# Sheet2.net
KiCad netlist of a schematic drawn in Altium Designer
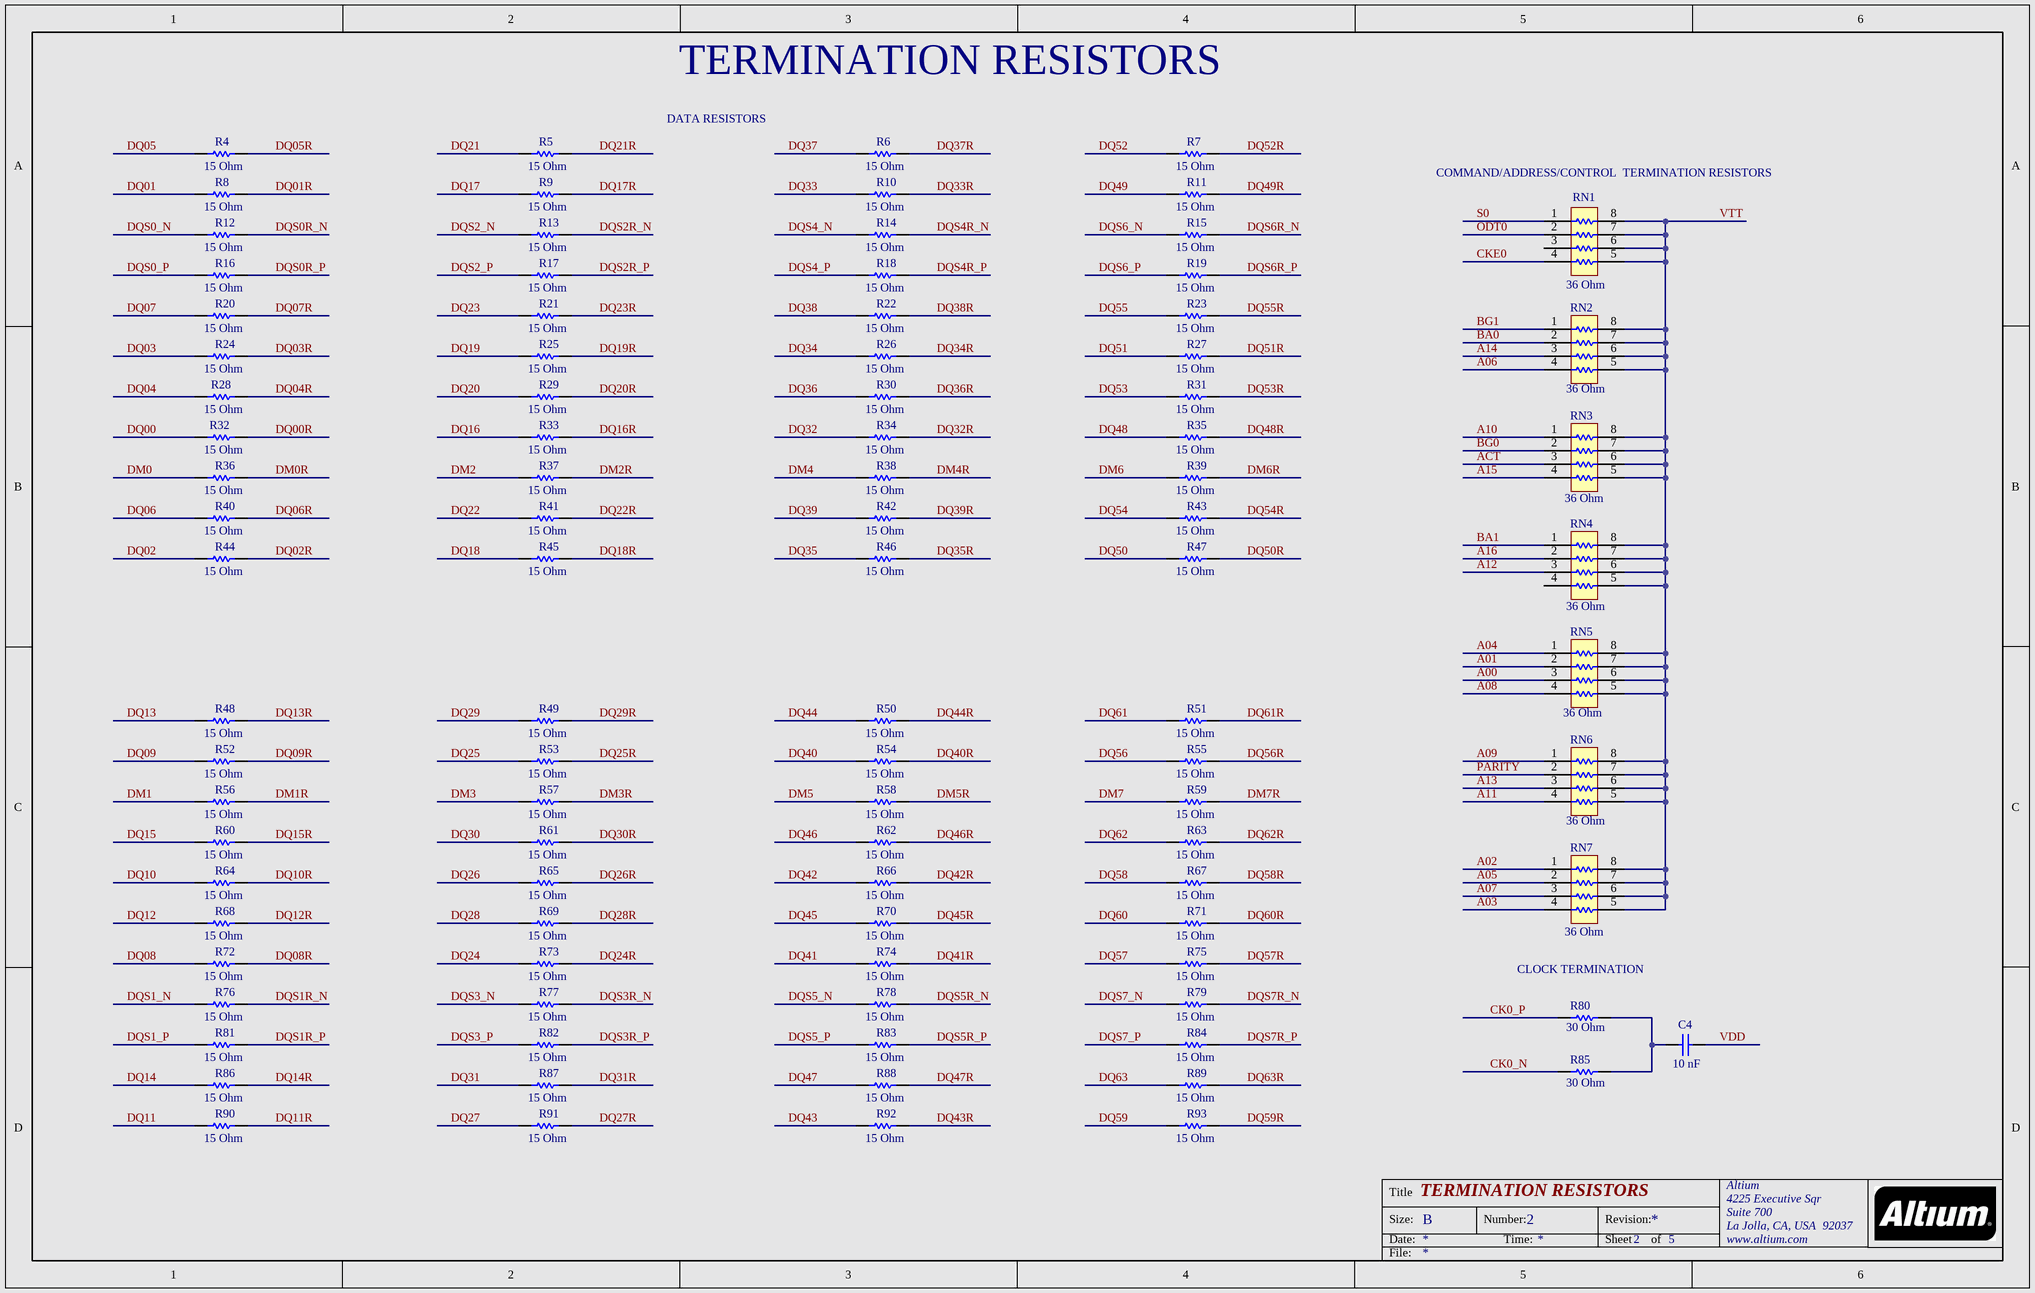
[diagram p0: Sheet2.SchDoc]

(export (version "E")
  (design (tool "Eeschema 10.0.6"))
  (components
    (comp (ref "C4")
      (value "C1005X7R1E103M050BB")
      (footprint "CAPC1005X55X10NL05")
      (description "Chip Capacitor, 10 nF, +/- 15%, 25 V, -55 to 125 degC, 0402 (1005 Metric), RoHS, Tape and Reel")
      (fields (field (name "TOLERANCE") "20%") (field (name "CAPACITANCE") "10 nF"))
      (libsource (lib "Altium Content Vault") (part "CMP-1663-00012-1"))
    )
    (comp (ref "R4")
      (value "ERJ-1GEJ150C")
      (footprint "RESC0603X26X15ML03T05")
      (description "Chip Resistor, 15 Ohm, +/- 5%, 0.05 W, -55 to 125 degC, 0201 (0603 Metric), RoHS, Tape and Reel")
      (fields (field (name "RESISTANCE") "15 Ohm") (field (name "TOLERANCE") "5%"))
      (libsource (lib "Altium Content Vault") (part "CMP-2004-03155-3"))
    )
    (comp (ref "R5")
      (value "ERJ-1GEJ150C")
      (footprint "RESC0603X26X15ML03T05")
      (description "Chip Resistor, 15 Ohm, +/- 5%, 0.05 W, -55 to 125 degC, 0201 (0603 Metric), RoHS, Tape and Reel")
      (fields (field (name "RESISTANCE") "15 Ohm") (field (name "TOLERANCE") "5%"))
      (libsource (lib "Altium Content Vault") (part "CMP-2004-03155-3"))
    )
    (comp (ref "R6")
      (value "ERJ-1GEJ150C")
      (footprint "RESC0603X26X15ML03T05")
      (description "Chip Resistor, 15 Ohm, +/- 5%, 0.05 W, -55 to 125 degC, 0201 (0603 Metric), RoHS, Tape and Reel")
      (fields (field (name "RESISTANCE") "15 Ohm") (field (name "TOLERANCE") "5%"))
      (libsource (lib "Altium Content Vault") (part "CMP-2004-03155-3"))
    )
    (comp (ref "R7")
      (value "ERJ-1GEJ150C")
      (footprint "RESC0603X26X15ML03T05")
      (description "Chip Resistor, 15 Ohm, +/- 5%, 0.05 W, -55 to 125 degC, 0201 (0603 Metric), RoHS, Tape and Reel")
      (fields (field (name "RESISTANCE") "15 Ohm") (field (name "TOLERANCE") "5%"))
      (libsource (lib "Altium Content Vault") (part "CMP-2004-03155-3"))
    )
    (comp (ref "R8")
      (value "ERJ-1GEJ150C")
      (footprint "RESC0603X26X15ML03T05")
      (description "Chip Resistor, 15 Ohm, +/- 5%, 0.05 W, -55 to 125 degC, 0201 (0603 Metric), RoHS, Tape and Reel")
      (fields (field (name "RESISTANCE") "15 Ohm") (field (name "TOLERANCE") "5%"))
      (libsource (lib "Altium Content Vault") (part "CMP-2004-03155-3"))
    )
    (comp (ref "R9")
      (value "ERJ-1GEJ150C")
      (footprint "RESC0603X26X15ML03T05")
      (description "Chip Resistor, 15 Ohm, +/- 5%, 0.05 W, -55 to 125 degC, 0201 (0603 Metric), RoHS, Tape and Reel")
      (fields (field (name "RESISTANCE") "15 Ohm") (field (name "TOLERANCE") "5%"))
      (libsource (lib "Altium Content Vault") (part "CMP-2004-03155-3"))
    )
    (comp (ref "R10")
      (value "ERJ-1GEJ150C")
      (footprint "RESC0603X26X15ML03T05")
      (description "Chip Resistor, 15 Ohm, +/- 5%, 0.05 W, -55 to 125 degC, 0201 (0603 Metric), RoHS, Tape and Reel")
      (fields (field (name "RESISTANCE") "15 Ohm") (field (name "TOLERANCE") "5%"))
      (libsource (lib "Altium Content Vault") (part "CMP-2004-03155-3"))
    )
    (comp (ref "R11")
      (value "ERJ-1GEJ150C")
      (footprint "RESC0603X26X15ML03T05")
      (description "Chip Resistor, 15 Ohm, +/- 5%, 0.05 W, -55 to 125 degC, 0201 (0603 Metric), RoHS, Tape and Reel")
      (fields (field (name "RESISTANCE") "15 Ohm") (field (name "TOLERANCE") "5%"))
      (libsource (lib "Altium Content Vault") (part "CMP-2004-03155-3"))
    )
    (comp (ref "R12")
      (value "ERJ-1GEJ150C")
      (footprint "RESC0603X26X15ML03T05")
      (description "Chip Resistor, 15 Ohm, +/- 5%, 0.05 W, -55 to 125 degC, 0201 (0603 Metric), RoHS, Tape and Reel")
      (fields (field (name "RESISTANCE") "15 Ohm") (field (name "TOLERANCE") "5%"))
      (libsource (lib "Altium Content Vault") (part "CMP-2004-03155-3"))
    )
    (comp (ref "R13")
      (value "ERJ-1GEJ150C")
      (footprint "RESC0603X26X15ML03T05")
      (description "Chip Resistor, 15 Ohm, +/- 5%, 0.05 W, -55 to 125 degC, 0201 (0603 Metric), RoHS, Tape and Reel")
      (fields (field (name "RESISTANCE") "15 Ohm") (field (name "TOLERANCE") "5%"))
      (libsource (lib "Altium Content Vault") (part "CMP-2004-03155-3"))
    )
    (comp (ref "R14")
      (value "ERJ-1GEJ150C")
      (footprint "RESC0603X26X15ML03T05")
      (description "Chip Resistor, 15 Ohm, +/- 5%, 0.05 W, -55 to 125 degC, 0201 (0603 Metric), RoHS, Tape and Reel")
      (fields (field (name "RESISTANCE") "15 Ohm") (field (name "TOLERANCE") "5%"))
      (libsource (lib "Altium Content Vault") (part "CMP-2004-03155-3"))
    )
    (comp (ref "R15")
      (value "ERJ-1GEJ150C")
      (footprint "RESC0603X26X15ML03T05")
      (description "Chip Resistor, 15 Ohm, +/- 5%, 0.05 W, -55 to 125 degC, 0201 (0603 Metric), RoHS, Tape and Reel")
      (fields (field (name "RESISTANCE") "15 Ohm") (field (name "TOLERANCE") "5%"))
      (libsource (lib "Altium Content Vault") (part "CMP-2004-03155-3"))
    )
    (comp (ref "R16")
      (value "ERJ-1GEJ150C")
      (footprint "RESC0603X26X15ML03T05")
      (description "Chip Resistor, 15 Ohm, +/- 5%, 0.05 W, -55 to 125 degC, 0201 (0603 Metric), RoHS, Tape and Reel")
      (fields (field (name "RESISTANCE") "15 Ohm") (field (name "TOLERANCE") "5%"))
      (libsource (lib "Altium Content Vault") (part "CMP-2004-03155-3"))
    )
    (comp (ref "R17")
      (value "ERJ-1GEJ150C")
      (footprint "RESC0603X26X15ML03T05")
      (description "Chip Resistor, 15 Ohm, +/- 5%, 0.05 W, -55 to 125 degC, 0201 (0603 Metric), RoHS, Tape and Reel")
      (fields (field (name "RESISTANCE") "15 Ohm") (field (name "TOLERANCE") "5%"))
      (libsource (lib "Altium Content Vault") (part "CMP-2004-03155-3"))
    )
    (comp (ref "R18")
      (value "ERJ-1GEJ150C")
      (footprint "RESC0603X26X15ML03T05")
      (description "Chip Resistor, 15 Ohm, +/- 5%, 0.05 W, -55 to 125 degC, 0201 (0603 Metric), RoHS, Tape and Reel")
      (fields (field (name "RESISTANCE") "15 Ohm") (field (name "TOLERANCE") "5%"))
      (libsource (lib "Altium Content Vault") (part "CMP-2004-03155-3"))
    )
    (comp (ref "R19")
      (value "ERJ-1GEJ150C")
      (footprint "RESC0603X26X15ML03T05")
      (description "Chip Resistor, 15 Ohm, +/- 5%, 0.05 W, -55 to 125 degC, 0201 (0603 Metric), RoHS, Tape and Reel")
      (fields (field (name "RESISTANCE") "15 Ohm") (field (name "TOLERANCE") "5%"))
      (libsource (lib "Altium Content Vault") (part "CMP-2004-03155-3"))
    )
    (comp (ref "R20")
      (value "ERJ-1GEJ150C")
      (footprint "RESC0603X26X15ML03T05")
      (description "Chip Resistor, 15 Ohm, +/- 5%, 0.05 W, -55 to 125 degC, 0201 (0603 Metric), RoHS, Tape and Reel")
      (fields (field (name "RESISTANCE") "15 Ohm") (field (name "TOLERANCE") "5%"))
      (libsource (lib "Altium Content Vault") (part "CMP-2004-03155-3"))
    )
    (comp (ref "R21")
      (value "ERJ-1GEJ150C")
      (footprint "RESC0603X26X15ML03T05")
      (description "Chip Resistor, 15 Ohm, +/- 5%, 0.05 W, -55 to 125 degC, 0201 (0603 Metric), RoHS, Tape and Reel")
      (fields (field (name "RESISTANCE") "15 Ohm") (field (name "TOLERANCE") "5%"))
      (libsource (lib "Altium Content Vault") (part "CMP-2004-03155-3"))
    )
    (comp (ref "R22")
      (value "ERJ-1GEJ150C")
      (footprint "RESC0603X26X15ML03T05")
      (description "Chip Resistor, 15 Ohm, +/- 5%, 0.05 W, -55 to 125 degC, 0201 (0603 Metric), RoHS, Tape and Reel")
      (fields (field (name "RESISTANCE") "15 Ohm") (field (name "TOLERANCE") "5%"))
      (libsource (lib "Altium Content Vault") (part "CMP-2004-03155-3"))
    )
    (comp (ref "R23")
      (value "ERJ-1GEJ150C")
      (footprint "RESC0603X26X15ML03T05")
      (description "Chip Resistor, 15 Ohm, +/- 5%, 0.05 W, -55 to 125 degC, 0201 (0603 Metric), RoHS, Tape and Reel")
      (fields (field (name "RESISTANCE") "15 Ohm") (field (name "TOLERANCE") "5%"))
      (libsource (lib "Altium Content Vault") (part "CMP-2004-03155-3"))
    )
    (comp (ref "R24")
      (value "ERJ-1GEJ150C")
      (footprint "RESC0603X26X15ML03T05")
      (description "Chip Resistor, 15 Ohm, +/- 5%, 0.05 W, -55 to 125 degC, 0201 (0603 Metric), RoHS, Tape and Reel")
      (fields (field (name "RESISTANCE") "15 Ohm") (field (name "TOLERANCE") "5%"))
      (libsource (lib "Altium Content Vault") (part "CMP-2004-03155-3"))
    )
    (comp (ref "R25")
      (value "ERJ-1GEJ150C")
      (footprint "RESC0603X26X15ML03T05")
      (description "Chip Resistor, 15 Ohm, +/- 5%, 0.05 W, -55 to 125 degC, 0201 (0603 Metric), RoHS, Tape and Reel")
      (fields (field (name "RESISTANCE") "15 Ohm") (field (name "TOLERANCE") "5%"))
      (libsource (lib "Altium Content Vault") (part "CMP-2004-03155-3"))
    )
    (comp (ref "R26")
      (value "ERJ-1GEJ150C")
      (footprint "RESC0603X26X15ML03T05")
      (description "Chip Resistor, 15 Ohm, +/- 5%, 0.05 W, -55 to 125 degC, 0201 (0603 Metric), RoHS, Tape and Reel")
      (fields (field (name "RESISTANCE") "15 Ohm") (field (name "TOLERANCE") "5%"))
      (libsource (lib "Altium Content Vault") (part "CMP-2004-03155-3"))
    )
    (comp (ref "R27")
      (value "ERJ-1GEJ150C")
      (footprint "RESC0603X26X15ML03T05")
      (description "Chip Resistor, 15 Ohm, +/- 5%, 0.05 W, -55 to 125 degC, 0201 (0603 Metric), RoHS, Tape and Reel")
      (fields (field (name "RESISTANCE") "15 Ohm") (field (name "TOLERANCE") "5%"))
      (libsource (lib "Altium Content Vault") (part "CMP-2004-03155-3"))
    )
    (comp (ref "R28")
      (value "ERJ-1GEJ150C")
      (footprint "RESC0603X26X15ML03T05")
      (description "Chip Resistor, 15 Ohm, +/- 5%, 0.05 W, -55 to 125 degC, 0201 (0603 Metric), RoHS, Tape and Reel")
      (fields (field (name "RESISTANCE") "15 Ohm") (field (name "TOLERANCE") "5%"))
      (libsource (lib "Altium Content Vault") (part "CMP-2004-03155-3"))
    )
    (comp (ref "R29")
      (value "ERJ-1GEJ150C")
      (footprint "RESC0603X26X15ML03T05")
      (description "Chip Resistor, 15 Ohm, +/- 5%, 0.05 W, -55 to 125 degC, 0201 (0603 Metric), RoHS, Tape and Reel")
      (fields (field (name "RESISTANCE") "15 Ohm") (field (name "TOLERANCE") "5%"))
      (libsource (lib "Altium Content Vault") (part "CMP-2004-03155-3"))
    )
    (comp (ref "R30")
      (value "ERJ-1GEJ150C")
      (footprint "RESC0603X26X15ML03T05")
      (description "Chip Resistor, 15 Ohm, +/- 5%, 0.05 W, -55 to 125 degC, 0201 (0603 Metric), RoHS, Tape and Reel")
      (fields (field (name "RESISTANCE") "15 Ohm") (field (name "TOLERANCE") "5%"))
      (libsource (lib "Altium Content Vault") (part "CMP-2004-03155-3"))
    )
    (comp (ref "R31")
      (value "ERJ-1GEJ150C")
      (footprint "RESC0603X26X15ML03T05")
      (description "Chip Resistor, 15 Ohm, +/- 5%, 0.05 W, -55 to 125 degC, 0201 (0603 Metric), RoHS, Tape and Reel")
      (fields (field (name "RESISTANCE") "15 Ohm") (field (name "TOLERANCE") "5%"))
      (libsource (lib "Altium Content Vault") (part "CMP-2004-03155-3"))
    )
    (comp (ref "R32")
      (value "ERJ-1GEJ150C")
      (footprint "RESC0603X26X15ML03T05")
      (description "Chip Resistor, 15 Ohm, +/- 5%, 0.05 W, -55 to 125 degC, 0201 (0603 Metric), RoHS, Tape and Reel")
      (fields (field (name "RESISTANCE") "15 Ohm") (field (name "TOLERANCE") "5%"))
      (libsource (lib "Altium Content Vault") (part "CMP-2004-03155-3"))
    )
    (comp (ref "R33")
      (value "ERJ-1GEJ150C")
      (footprint "RESC0603X26X15ML03T05")
      (description "Chip Resistor, 15 Ohm, +/- 5%, 0.05 W, -55 to 125 degC, 0201 (0603 Metric), RoHS, Tape and Reel")
      (fields (field (name "RESISTANCE") "15 Ohm") (field (name "TOLERANCE") "5%"))
      (libsource (lib "Altium Content Vault") (part "CMP-2004-03155-3"))
    )
    (comp (ref "R34")
      (value "ERJ-1GEJ150C")
      (footprint "RESC0603X26X15ML03T05")
      (description "Chip Resistor, 15 Ohm, +/- 5%, 0.05 W, -55 to 125 degC, 0201 (0603 Metric), RoHS, Tape and Reel")
      (fields (field (name "RESISTANCE") "15 Ohm") (field (name "TOLERANCE") "5%"))
      (libsource (lib "Altium Content Vault") (part "CMP-2004-03155-3"))
    )
    (comp (ref "R35")
      (value "ERJ-1GEJ150C")
      (footprint "RESC0603X26X15ML03T05")
      (description "Chip Resistor, 15 Ohm, +/- 5%, 0.05 W, -55 to 125 degC, 0201 (0603 Metric), RoHS, Tape and Reel")
      (fields (field (name "RESISTANCE") "15 Ohm") (field (name "TOLERANCE") "5%"))
      (libsource (lib "Altium Content Vault") (part "CMP-2004-03155-3"))
    )
    (comp (ref "R36")
      (value "ERJ-1GEJ150C")
      (footprint "RESC0603X26X15ML03T05")
      (description "Chip Resistor, 15 Ohm, +/- 5%, 0.05 W, -55 to 125 degC, 0201 (0603 Metric), RoHS, Tape and Reel")
      (fields (field (name "RESISTANCE") "15 Ohm") (field (name "TOLERANCE") "5%"))
      (libsource (lib "Altium Content Vault") (part "CMP-2004-03155-3"))
    )
    (comp (ref "R37")
      (value "ERJ-1GEJ150C")
      (footprint "RESC0603X26X15ML03T05")
      (description "Chip Resistor, 15 Ohm, +/- 5%, 0.05 W, -55 to 125 degC, 0201 (0603 Metric), RoHS, Tape and Reel")
      (fields (field (name "RESISTANCE") "15 Ohm") (field (name "TOLERANCE") "5%"))
      (libsource (lib "Altium Content Vault") (part "CMP-2004-03155-3"))
    )
    (comp (ref "R38")
      (value "ERJ-1GEJ150C")
      (footprint "RESC0603X26X15ML03T05")
      (description "Chip Resistor, 15 Ohm, +/- 5%, 0.05 W, -55 to 125 degC, 0201 (0603 Metric), RoHS, Tape and Reel")
      (fields (field (name "RESISTANCE") "15 Ohm") (field (name "TOLERANCE") "5%"))
      (libsource (lib "Altium Content Vault") (part "CMP-2004-03155-3"))
    )
    (comp (ref "R39")
      (value "ERJ-1GEJ150C")
      (footprint "RESC0603X26X15ML03T05")
      (description "Chip Resistor, 15 Ohm, +/- 5%, 0.05 W, -55 to 125 degC, 0201 (0603 Metric), RoHS, Tape and Reel")
      (fields (field (name "RESISTANCE") "15 Ohm") (field (name "TOLERANCE") "5%"))
      (libsource (lib "Altium Content Vault") (part "CMP-2004-03155-3"))
    )
    (comp (ref "R40")
      (value "ERJ-1GEJ150C")
      (footprint "RESC0603X26X15ML03T05")
      (description "Chip Resistor, 15 Ohm, +/- 5%, 0.05 W, -55 to 125 degC, 0201 (0603 Metric), RoHS, Tape and Reel")
      (fields (field (name "RESISTANCE") "15 Ohm") (field (name "TOLERANCE") "5%"))
      (libsource (lib "Altium Content Vault") (part "CMP-2004-03155-3"))
    )
    (comp (ref "R41")
      (value "ERJ-1GEJ150C")
      (footprint "RESC0603X26X15ML03T05")
      (description "Chip Resistor, 15 Ohm, +/- 5%, 0.05 W, -55 to 125 degC, 0201 (0603 Metric), RoHS, Tape and Reel")
      (fields (field (name "RESISTANCE") "15 Ohm") (field (name "TOLERANCE") "5%"))
      (libsource (lib "Altium Content Vault") (part "CMP-2004-03155-3"))
    )
    (comp (ref "R42")
      (value "ERJ-1GEJ150C")
      (footprint "RESC0603X26X15ML03T05")
      (description "Chip Resistor, 15 Ohm, +/- 5%, 0.05 W, -55 to 125 degC, 0201 (0603 Metric), RoHS, Tape and Reel")
      (fields (field (name "RESISTANCE") "15 Ohm") (field (name "TOLERANCE") "5%"))
      (libsource (lib "Altium Content Vault") (part "CMP-2004-03155-3"))
    )
    (comp (ref "R43")
      (value "ERJ-1GEJ150C")
      (footprint "RESC0603X26X15ML03T05")
      (description "Chip Resistor, 15 Ohm, +/- 5%, 0.05 W, -55 to 125 degC, 0201 (0603 Metric), RoHS, Tape and Reel")
      (fields (field (name "RESISTANCE") "15 Ohm") (field (name "TOLERANCE") "5%"))
      (libsource (lib "Altium Content Vault") (part "CMP-2004-03155-3"))
    )
    (comp (ref "R44")
      (value "ERJ-1GEJ150C")
      (footprint "RESC0603X26X15ML03T05")
      (description "Chip Resistor, 15 Ohm, +/- 5%, 0.05 W, -55 to 125 degC, 0201 (0603 Metric), RoHS, Tape and Reel")
      (fields (field (name "RESISTANCE") "15 Ohm") (field (name "TOLERANCE") "5%"))
      (libsource (lib "Altium Content Vault") (part "CMP-2004-03155-3"))
    )
    (comp (ref "R45")
      (value "ERJ-1GEJ150C")
      (footprint "RESC0603X26X15ML03T05")
      (description "Chip Resistor, 15 Ohm, +/- 5%, 0.05 W, -55 to 125 degC, 0201 (0603 Metric), RoHS, Tape and Reel")
      (fields (field (name "RESISTANCE") "15 Ohm") (field (name "TOLERANCE") "5%"))
      (libsource (lib "Altium Content Vault") (part "CMP-2004-03155-3"))
    )
    (comp (ref "R46")
      (value "ERJ-1GEJ150C")
      (footprint "RESC0603X26X15ML03T05")
      (description "Chip Resistor, 15 Ohm, +/- 5%, 0.05 W, -55 to 125 degC, 0201 (0603 Metric), RoHS, Tape and Reel")
      (fields (field (name "RESISTANCE") "15 Ohm") (field (name "TOLERANCE") "5%"))
      (libsource (lib "Altium Content Vault") (part "CMP-2004-03155-3"))
    )
    (comp (ref "R47")
      (value "ERJ-1GEJ150C")
      (footprint "RESC0603X26X15ML03T05")
      (description "Chip Resistor, 15 Ohm, +/- 5%, 0.05 W, -55 to 125 degC, 0201 (0603 Metric), RoHS, Tape and Reel")
      (fields (field (name "RESISTANCE") "15 Ohm") (field (name "TOLERANCE") "5%"))
      (libsource (lib "Altium Content Vault") (part "CMP-2004-03155-3"))
    )
    (comp (ref "R48")
      (value "ERJ-1GEJ150C")
      (footprint "RESC0603X26X15ML03T05")
      (description "Chip Resistor, 15 Ohm, +/- 5%, 0.05 W, -55 to 125 degC, 0201 (0603 Metric), RoHS, Tape and Reel")
      (fields (field (name "RESISTANCE") "15 Ohm") (field (name "TOLERANCE") "5%"))
      (libsource (lib "Altium Content Vault") (part "CMP-2004-03155-3"))
    )
    (comp (ref "R49")
      (value "ERJ-1GEJ150C")
      (footprint "RESC0603X26X15ML03T05")
      (description "Chip Resistor, 15 Ohm, +/- 5%, 0.05 W, -55 to 125 degC, 0201 (0603 Metric), RoHS, Tape and Reel")
      (fields (field (name "RESISTANCE") "15 Ohm") (field (name "TOLERANCE") "5%"))
      (libsource (lib "Altium Content Vault") (part "CMP-2004-03155-3"))
    )
    (comp (ref "R50")
      (value "ERJ-1GEJ150C")
      (footprint "RESC0603X26X15ML03T05")
      (description "Chip Resistor, 15 Ohm, +/- 5%, 0.05 W, -55 to 125 degC, 0201 (0603 Metric), RoHS, Tape and Reel")
      (fields (field (name "RESISTANCE") "15 Ohm") (field (name "TOLERANCE") "5%"))
      (libsource (lib "Altium Content Vault") (part "CMP-2004-03155-3"))
    )
    (comp (ref "R51")
      (value "ERJ-1GEJ150C")
      (footprint "RESC0603X26X15ML03T05")
      (description "Chip Resistor, 15 Ohm, +/- 5%, 0.05 W, -55 to 125 degC, 0201 (0603 Metric), RoHS, Tape and Reel")
      (fields (field (name "RESISTANCE") "15 Ohm") (field (name "TOLERANCE") "5%"))
      (libsource (lib "Altium Content Vault") (part "CMP-2004-03155-3"))
    )
    (comp (ref "R52")
      (value "ERJ-1GEJ150C")
      (footprint "RESC0603X26X15ML03T05")
      (description "Chip Resistor, 15 Ohm, +/- 5%, 0.05 W, -55 to 125 degC, 0201 (0603 Metric), RoHS, Tape and Reel")
      (fields (field (name "RESISTANCE") "15 Ohm") (field (name "TOLERANCE") "5%"))
      (libsource (lib "Altium Content Vault") (part "CMP-2004-03155-3"))
    )
    (comp (ref "R53")
      (value "ERJ-1GEJ150C")
      (footprint "RESC0603X26X15ML03T05")
      (description "Chip Resistor, 15 Ohm, +/- 5%, 0.05 W, -55 to 125 degC, 0201 (0603 Metric), RoHS, Tape and Reel")
      (fields (field (name "RESISTANCE") "15 Ohm") (field (name "TOLERANCE") "5%"))
      (libsource (lib "Altium Content Vault") (part "CMP-2004-03155-3"))
    )
    (comp (ref "R54")
      (value "ERJ-1GEJ150C")
      (footprint "RESC0603X26X15ML03T05")
      (description "Chip Resistor, 15 Ohm, +/- 5%, 0.05 W, -55 to 125 degC, 0201 (0603 Metric), RoHS, Tape and Reel")
      (fields (field (name "RESISTANCE") "15 Ohm") (field (name "TOLERANCE") "5%"))
      (libsource (lib "Altium Content Vault") (part "CMP-2004-03155-3"))
    )
    (comp (ref "R55")
      (value "ERJ-1GEJ150C")
      (footprint "RESC0603X26X15ML03T05")
      (description "Chip Resistor, 15 Ohm, +/- 5%, 0.05 W, -55 to 125 degC, 0201 (0603 Metric), RoHS, Tape and Reel")
      (fields (field (name "RESISTANCE") "15 Ohm") (field (name "TOLERANCE") "5%"))
      (libsource (lib "Altium Content Vault") (part "CMP-2004-03155-3"))
    )
    (comp (ref "R56")
      (value "ERJ-1GEJ150C")
      (footprint "RESC0603X26X15ML03T05")
      (description "Chip Resistor, 15 Ohm, +/- 5%, 0.05 W, -55 to 125 degC, 0201 (0603 Metric), RoHS, Tape and Reel")
      (fields (field (name "RESISTANCE") "15 Ohm") (field (name "TOLERANCE") "5%"))
      (libsource (lib "Altium Content Vault") (part "CMP-2004-03155-3"))
    )
    (comp (ref "R57")
      (value "ERJ-1GEJ150C")
      (footprint "RESC0603X26X15ML03T05")
      (description "Chip Resistor, 15 Ohm, +/- 5%, 0.05 W, -55 to 125 degC, 0201 (0603 Metric), RoHS, Tape and Reel")
      (fields (field (name "RESISTANCE") "15 Ohm") (field (name "TOLERANCE") "5%"))
      (libsource (lib "Altium Content Vault") (part "CMP-2004-03155-3"))
    )
    (comp (ref "R58")
      (value "ERJ-1GEJ150C")
      (footprint "RESC0603X26X15ML03T05")
      (description "Chip Resistor, 15 Ohm, +/- 5%, 0.05 W, -55 to 125 degC, 0201 (0603 Metric), RoHS, Tape and Reel")
      (fields (field (name "RESISTANCE") "15 Ohm") (field (name "TOLERANCE") "5%"))
      (libsource (lib "Altium Content Vault") (part "CMP-2004-03155-3"))
    )
    (comp (ref "R59")
      (value "ERJ-1GEJ150C")
      (footprint "RESC0603X26X15ML03T05")
      (description "Chip Resistor, 15 Ohm, +/- 5%, 0.05 W, -55 to 125 degC, 0201 (0603 Metric), RoHS, Tape and Reel")
      (fields (field (name "RESISTANCE") "15 Ohm") (field (name "TOLERANCE") "5%"))
      (libsource (lib "Altium Content Vault") (part "CMP-2004-03155-3"))
    )
    (comp (ref "R60")
      (value "ERJ-1GEJ150C")
      (footprint "RESC0603X26X15ML03T05")
      (description "Chip Resistor, 15 Ohm, +/- 5%, 0.05 W, -55 to 125 degC, 0201 (0603 Metric), RoHS, Tape and Reel")
      (fields (field (name "RESISTANCE") "15 Ohm") (field (name "TOLERANCE") "5%"))
      (libsource (lib "Altium Content Vault") (part "CMP-2004-03155-3"))
    )
    (comp (ref "R61")
      (value "ERJ-1GEJ150C")
      (footprint "RESC0603X26X15ML03T05")
      (description "Chip Resistor, 15 Ohm, +/- 5%, 0.05 W, -55 to 125 degC, 0201 (0603 Metric), RoHS, Tape and Reel")
      (fields (field (name "RESISTANCE") "15 Ohm") (field (name "TOLERANCE") "5%"))
      (libsource (lib "Altium Content Vault") (part "CMP-2004-03155-3"))
    )
    (comp (ref "R62")
      (value "ERJ-1GEJ150C")
      (footprint "RESC0603X26X15ML03T05")
      (description "Chip Resistor, 15 Ohm, +/- 5%, 0.05 W, -55 to 125 degC, 0201 (0603 Metric), RoHS, Tape and Reel")
      (fields (field (name "RESISTANCE") "15 Ohm") (field (name "TOLERANCE") "5%"))
      (libsource (lib "Altium Content Vault") (part "CMP-2004-03155-3"))
    )
    (comp (ref "R63")
      (value "ERJ-1GEJ150C")
      (footprint "RESC0603X26X15ML03T05")
      (description "Chip Resistor, 15 Ohm, +/- 5%, 0.05 W, -55 to 125 degC, 0201 (0603 Metric), RoHS, Tape and Reel")
      (fields (field (name "RESISTANCE") "15 Ohm") (field (name "TOLERANCE") "5%"))
      (libsource (lib "Altium Content Vault") (part "CMP-2004-03155-3"))
    )
    (comp (ref "R64")
      (value "ERJ-1GEJ150C")
      (footprint "RESC0603X26X15ML03T05")
      (description "Chip Resistor, 15 Ohm, +/- 5%, 0.05 W, -55 to 125 degC, 0201 (0603 Metric), RoHS, Tape and Reel")
      (fields (field (name "RESISTANCE") "15 Ohm") (field (name "TOLERANCE") "5%"))
      (libsource (lib "Altium Content Vault") (part "CMP-2004-03155-3"))
    )
    (comp (ref "R65")
      (value "ERJ-1GEJ150C")
      (footprint "RESC0603X26X15ML03T05")
      (description "Chip Resistor, 15 Ohm, +/- 5%, 0.05 W, -55 to 125 degC, 0201 (0603 Metric), RoHS, Tape and Reel")
      (fields (field (name "RESISTANCE") "15 Ohm") (field (name "TOLERANCE") "5%"))
      (libsource (lib "Altium Content Vault") (part "CMP-2004-03155-3"))
    )
    (comp (ref "R66")
      (value "ERJ-1GEJ150C")
      (footprint "RESC0603X26X15ML03T05")
      (description "Chip Resistor, 15 Ohm, +/- 5%, 0.05 W, -55 to 125 degC, 0201 (0603 Metric), RoHS, Tape and Reel")
      (fields (field (name "RESISTANCE") "15 Ohm") (field (name "TOLERANCE") "5%"))
      (libsource (lib "Altium Content Vault") (part "CMP-2004-03155-3"))
    )
    (comp (ref "R67")
      (value "ERJ-1GEJ150C")
      (footprint "RESC0603X26X15ML03T05")
      (description "Chip Resistor, 15 Ohm, +/- 5%, 0.05 W, -55 to 125 degC, 0201 (0603 Metric), RoHS, Tape and Reel")
      (fields (field (name "RESISTANCE") "15 Ohm") (field (name "TOLERANCE") "5%"))
      (libsource (lib "Altium Content Vault") (part "CMP-2004-03155-3"))
    )
    (comp (ref "R68")
      (value "ERJ-1GEJ150C")
      (footprint "RESC0603X26X15ML03T05")
      (description "Chip Resistor, 15 Ohm, +/- 5%, 0.05 W, -55 to 125 degC, 0201 (0603 Metric), RoHS, Tape and Reel")
      (fields (field (name "RESISTANCE") "15 Ohm") (field (name "TOLERANCE") "5%"))
      (libsource (lib "Altium Content Vault") (part "CMP-2004-03155-3"))
    )
    (comp (ref "R69")
      (value "ERJ-1GEJ150C")
      (footprint "RESC0603X26X15ML03T05")
      (description "Chip Resistor, 15 Ohm, +/- 5%, 0.05 W, -55 to 125 degC, 0201 (0603 Metric), RoHS, Tape and Reel")
      (fields (field (name "RESISTANCE") "15 Ohm") (field (name "TOLERANCE") "5%"))
      (libsource (lib "Altium Content Vault") (part "CMP-2004-03155-3"))
    )
    (comp (ref "R70")
      (value "ERJ-1GEJ150C")
      (footprint "RESC0603X26X15ML03T05")
      (description "Chip Resistor, 15 Ohm, +/- 5%, 0.05 W, -55 to 125 degC, 0201 (0603 Metric), RoHS, Tape and Reel")
      (fields (field (name "RESISTANCE") "15 Ohm") (field (name "TOLERANCE") "5%"))
      (libsource (lib "Altium Content Vault") (part "CMP-2004-03155-3"))
    )
    (comp (ref "R71")
      (value "ERJ-1GEJ150C")
      (footprint "RESC0603X26X15ML03T05")
      (description "Chip Resistor, 15 Ohm, +/- 5%, 0.05 W, -55 to 125 degC, 0201 (0603 Metric), RoHS, Tape and Reel")
      (fields (field (name "RESISTANCE") "15 Ohm") (field (name "TOLERANCE") "5%"))
      (libsource (lib "Altium Content Vault") (part "CMP-2004-03155-3"))
    )
    (comp (ref "R72")
      (value "ERJ-1GEJ150C")
      (footprint "RESC0603X26X15ML03T05")
      (description "Chip Resistor, 15 Ohm, +/- 5%, 0.05 W, -55 to 125 degC, 0201 (0603 Metric), RoHS, Tape and Reel")
      (fields (field (name "RESISTANCE") "15 Ohm") (field (name "TOLERANCE") "5%"))
      (libsource (lib "Altium Content Vault") (part "CMP-2004-03155-3"))
    )
    (comp (ref "R73")
      (value "ERJ-1GEJ150C")
      (footprint "RESC0603X26X15ML03T05")
      (description "Chip Resistor, 15 Ohm, +/- 5%, 0.05 W, -55 to 125 degC, 0201 (0603 Metric), RoHS, Tape and Reel")
      (fields (field (name "RESISTANCE") "15 Ohm") (field (name "TOLERANCE") "5%"))
      (libsource (lib "Altium Content Vault") (part "CMP-2004-03155-3"))
    )
    (comp (ref "R74")
      (value "ERJ-1GEJ150C")
      (footprint "RESC0603X26X15ML03T05")
      (description "Chip Resistor, 15 Ohm, +/- 5%, 0.05 W, -55 to 125 degC, 0201 (0603 Metric), RoHS, Tape and Reel")
      (fields (field (name "RESISTANCE") "15 Ohm") (field (name "TOLERANCE") "5%"))
      (libsource (lib "Altium Content Vault") (part "CMP-2004-03155-3"))
    )
    (comp (ref "R75")
      (value "ERJ-1GEJ150C")
      (footprint "RESC0603X26X15ML03T05")
      (description "Chip Resistor, 15 Ohm, +/- 5%, 0.05 W, -55 to 125 degC, 0201 (0603 Metric), RoHS, Tape and Reel")
      (fields (field (name "RESISTANCE") "15 Ohm") (field (name "TOLERANCE") "5%"))
      (libsource (lib "Altium Content Vault") (part "CMP-2004-03155-3"))
    )
    (comp (ref "R76")
      (value "ERJ-1GEJ150C")
      (footprint "RESC0603X26X15ML03T05")
      (description "Chip Resistor, 15 Ohm, +/- 5%, 0.05 W, -55 to 125 degC, 0201 (0603 Metric), RoHS, Tape and Reel")
      (fields (field (name "RESISTANCE") "15 Ohm") (field (name "TOLERANCE") "5%"))
      (libsource (lib "Altium Content Vault") (part "CMP-2004-03155-3"))
    )
    (comp (ref "R77")
      (value "ERJ-1GEJ150C")
      (footprint "RESC0603X26X15ML03T05")
      (description "Chip Resistor, 15 Ohm, +/- 5%, 0.05 W, -55 to 125 degC, 0201 (0603 Metric), RoHS, Tape and Reel")
      (fields (field (name "RESISTANCE") "15 Ohm") (field (name "TOLERANCE") "5%"))
      (libsource (lib "Altium Content Vault") (part "CMP-2004-03155-3"))
    )
    (comp (ref "R78")
      (value "ERJ-1GEJ150C")
      (footprint "RESC0603X26X15ML03T05")
      (description "Chip Resistor, 15 Ohm, +/- 5%, 0.05 W, -55 to 125 degC, 0201 (0603 Metric), RoHS, Tape and Reel")
      (fields (field (name "RESISTANCE") "15 Ohm") (field (name "TOLERANCE") "5%"))
      (libsource (lib "Altium Content Vault") (part "CMP-2004-03155-3"))
    )
    (comp (ref "R79")
      (value "ERJ-1GEJ150C")
      (footprint "RESC0603X26X15ML03T05")
      (description "Chip Resistor, 15 Ohm, +/- 5%, 0.05 W, -55 to 125 degC, 0201 (0603 Metric), RoHS, Tape and Reel")
      (fields (field (name "RESISTANCE") "15 Ohm") (field (name "TOLERANCE") "5%"))
      (libsource (lib "Altium Content Vault") (part "CMP-2004-03155-3"))
    )
    (comp (ref "R80")
      (value "RC0402JR-0730RL")
      (footprint "RESC1005X40X25NL5T10")
      (description "Chip Resistor, 30 Ohm, +/- 5%, 0.063 W, -55 to 155 degC, 0402 (1005 Metric), RoHS, Tape and Reel")
      (fields (field (name "RESISTANCE") "30 Ohm") (field (name "TOLERANCE") "5%"))
      (libsource (lib "Altium Content Vault") (part "CMP-2002-07983-2"))
    )
    (comp (ref "R81")
      (value "ERJ-1GEJ150C")
      (footprint "RESC0603X26X15ML03T05")
      (description "Chip Resistor, 15 Ohm, +/- 5%, 0.05 W, -55 to 125 degC, 0201 (0603 Metric), RoHS, Tape and Reel")
      (fields (field (name "RESISTANCE") "15 Ohm") (field (name "TOLERANCE") "5%"))
      (libsource (lib "Altium Content Vault") (part "CMP-2004-03155-3"))
    )
    (comp (ref "R82")
      (value "ERJ-1GEJ150C")
      (footprint "RESC0603X26X15ML03T05")
      (description "Chip Resistor, 15 Ohm, +/- 5%, 0.05 W, -55 to 125 degC, 0201 (0603 Metric), RoHS, Tape and Reel")
      (fields (field (name "RESISTANCE") "15 Ohm") (field (name "TOLERANCE") "5%"))
      (libsource (lib "Altium Content Vault") (part "CMP-2004-03155-3"))
    )
    (comp (ref "R83")
      (value "ERJ-1GEJ150C")
      (footprint "RESC0603X26X15ML03T05")
      (description "Chip Resistor, 15 Ohm, +/- 5%, 0.05 W, -55 to 125 degC, 0201 (0603 Metric), RoHS, Tape and Reel")
      (fields (field (name "RESISTANCE") "15 Ohm") (field (name "TOLERANCE") "5%"))
      (libsource (lib "Altium Content Vault") (part "CMP-2004-03155-3"))
    )
    (comp (ref "R84")
      (value "ERJ-1GEJ150C")
      (footprint "RESC0603X26X15ML03T05")
      (description "Chip Resistor, 15 Ohm, +/- 5%, 0.05 W, -55 to 125 degC, 0201 (0603 Metric), RoHS, Tape and Reel")
      (fields (field (name "RESISTANCE") "15 Ohm") (field (name "TOLERANCE") "5%"))
      (libsource (lib "Altium Content Vault") (part "CMP-2004-03155-3"))
    )
    (comp (ref "R85")
      (value "RC0402JR-0730RL")
      (footprint "RESC1005X40X25NL5T10")
      (description "Chip Resistor, 30 Ohm, +/- 5%, 0.063 W, -55 to 155 degC, 0402 (1005 Metric), RoHS, Tape and Reel")
      (fields (field (name "RESISTANCE") "30 Ohm") (field (name "TOLERANCE") "5%"))
      (libsource (lib "Altium Content Vault") (part "CMP-2002-07983-2"))
    )
    (comp (ref "R86")
      (value "ERJ-1GEJ150C")
      (footprint "RESC0603X26X15ML03T05")
      (description "Chip Resistor, 15 Ohm, +/- 5%, 0.05 W, -55 to 125 degC, 0201 (0603 Metric), RoHS, Tape and Reel")
      (fields (field (name "RESISTANCE") "15 Ohm") (field (name "TOLERANCE") "5%"))
      (libsource (lib "Altium Content Vault") (part "CMP-2004-03155-3"))
    )
    (comp (ref "R87")
      (value "ERJ-1GEJ150C")
      (footprint "RESC0603X26X15ML03T05")
      (description "Chip Resistor, 15 Ohm, +/- 5%, 0.05 W, -55 to 125 degC, 0201 (0603 Metric), RoHS, Tape and Reel")
      (fields (field (name "RESISTANCE") "15 Ohm") (field (name "TOLERANCE") "5%"))
      (libsource (lib "Altium Content Vault") (part "CMP-2004-03155-3"))
    )
    (comp (ref "R88")
      (value "ERJ-1GEJ150C")
      (footprint "RESC0603X26X15ML03T05")
      (description "Chip Resistor, 15 Ohm, +/- 5%, 0.05 W, -55 to 125 degC, 0201 (0603 Metric), RoHS, Tape and Reel")
      (fields (field (name "RESISTANCE") "15 Ohm") (field (name "TOLERANCE") "5%"))
      (libsource (lib "Altium Content Vault") (part "CMP-2004-03155-3"))
    )
    (comp (ref "R89")
      (value "ERJ-1GEJ150C")
      (footprint "RESC0603X26X15ML03T05")
      (description "Chip Resistor, 15 Ohm, +/- 5%, 0.05 W, -55 to 125 degC, 0201 (0603 Metric), RoHS, Tape and Reel")
      (fields (field (name "RESISTANCE") "15 Ohm") (field (name "TOLERANCE") "5%"))
      (libsource (lib "Altium Content Vault") (part "CMP-2004-03155-3"))
    )
    (comp (ref "R90")
      (value "ERJ-1GEJ150C")
      (footprint "RESC0603X26X15ML03T05")
      (description "Chip Resistor, 15 Ohm, +/- 5%, 0.05 W, -55 to 125 degC, 0201 (0603 Metric), RoHS, Tape and Reel")
      (fields (field (name "RESISTANCE") "15 Ohm") (field (name "TOLERANCE") "5%"))
      (libsource (lib "Altium Content Vault") (part "CMP-2004-03155-3"))
    )
    (comp (ref "R91")
      (value "ERJ-1GEJ150C")
      (footprint "RESC0603X26X15ML03T05")
      (description "Chip Resistor, 15 Ohm, +/- 5%, 0.05 W, -55 to 125 degC, 0201 (0603 Metric), RoHS, Tape and Reel")
      (fields (field (name "RESISTANCE") "15 Ohm") (field (name "TOLERANCE") "5%"))
      (libsource (lib "Altium Content Vault") (part "CMP-2004-03155-3"))
    )
    (comp (ref "R92")
      (value "ERJ-1GEJ150C")
      (footprint "RESC0603X26X15ML03T05")
      (description "Chip Resistor, 15 Ohm, +/- 5%, 0.05 W, -55 to 125 degC, 0201 (0603 Metric), RoHS, Tape and Reel")
      (fields (field (name "RESISTANCE") "15 Ohm") (field (name "TOLERANCE") "5%"))
      (libsource (lib "Altium Content Vault") (part "CMP-2004-03155-3"))
    )
    (comp (ref "R93")
      (value "ERJ-1GEJ150C")
      (footprint "RESC0603X26X15ML03T05")
      (description "Chip Resistor, 15 Ohm, +/- 5%, 0.05 W, -55 to 125 degC, 0201 (0603 Metric), RoHS, Tape and Reel")
      (fields (field (name "RESISTANCE") "15 Ohm") (field (name "TOLERANCE") "5%"))
      (libsource (lib "Altium Content Vault") (part "CMP-2004-03155-3"))
    )
    (comp (ref "RN1")
      (value "CAY10-360J4LF")
      (footprint "BOUR-CAY10-J4_V")
      (description "Chip Resistor Array, 36 Ohm, +/- 5%, 62.5 mW, -55 to 125 degC, 8-Pin SMD, RoHS, Tape and Reel")
      (fields (field (name "RESISTANCE") "36 Ohm") (field (name "TOLERANCE") "5%"))
      (libsource (lib "Altium Content Vault") (part "CMP-1734-00001-1"))
    )
    (comp (ref "RN2")
      (value "CAY10-360J4LF")
      (footprint "BOUR-CAY10-J4_V")
      (description "Chip Resistor Array, 36 Ohm, +/- 5%, 62.5 mW, -55 to 125 degC, 8-Pin SMD, RoHS, Tape and Reel")
      (fields (field (name "RESISTANCE") "36 Ohm") (field (name "TOLERANCE") "5%"))
      (libsource (lib "Altium Content Vault") (part "CMP-1734-00001-1"))
    )
    (comp (ref "RN3")
      (value "CAY10-360J4LF")
      (footprint "BOUR-CAY10-J4_V")
      (description "Chip Resistor Array, 36 Ohm, +/- 5%, 62.5 mW, -55 to 125 degC, 8-Pin SMD, RoHS, Tape and Reel")
      (fields (field (name "RESISTANCE") "36 Ohm") (field (name "TOLERANCE") "5%"))
      (libsource (lib "Altium Content Vault") (part "CMP-1734-00001-1"))
    )
    (comp (ref "RN4")
      (value "CAY10-360J4LF")
      (footprint "BOUR-CAY10-J4_V")
      (description "Chip Resistor Array, 36 Ohm, +/- 5%, 62.5 mW, -55 to 125 degC, 8-Pin SMD, RoHS, Tape and Reel")
      (fields (field (name "RESISTANCE") "36 Ohm") (field (name "TOLERANCE") "5%"))
      (libsource (lib "Altium Content Vault") (part "CMP-1734-00001-1"))
    )
    (comp (ref "RN5")
      (value "CAY10-360J4LF")
      (footprint "BOUR-CAY10-J4_V")
      (description "Chip Resistor Array, 36 Ohm, +/- 5%, 62.5 mW, -55 to 125 degC, 8-Pin SMD, RoHS, Tape and Reel")
      (fields (field (name "RESISTANCE") "36 Ohm") (field (name "TOLERANCE") "5%"))
      (libsource (lib "Altium Content Vault") (part "CMP-1734-00001-1"))
    )
    (comp (ref "RN6")
      (value "CAY10-360J4LF")
      (footprint "BOUR-CAY10-J4_V")
      (description "Chip Resistor Array, 36 Ohm, +/- 5%, 62.5 mW, -55 to 125 degC, 8-Pin SMD, RoHS, Tape and Reel")
      (fields (field (name "RESISTANCE") "36 Ohm") (field (name "TOLERANCE") "5%"))
      (libsource (lib "Altium Content Vault") (part "CMP-1734-00001-1"))
    )
    (comp (ref "RN7")
      (value "CAY10-360J4LF")
      (footprint "BOUR-CAY10-J4_V")
      (description "Chip Resistor Array, 36 Ohm, +/- 5%, 62.5 mW, -55 to 125 degC, 8-Pin SMD, RoHS, Tape and Reel")
      (fields (field (name "RESISTANCE") "36 Ohm") (field (name "TOLERANCE") "5%"))
      (libsource (lib "Altium Content Vault") (part "CMP-1734-00001-1"))
    )
  )
  (nets
    (net (code "1") (name "/A00") (class "Default")
      (node (ref "RN5") (pin "3") (pinfunction "3_3") (pintype "passive"))
    )
    (net (code "2") (name "/A01") (class "Default")
      (node (ref "RN5") (pin "2") (pinfunction "2_2") (pintype "passive"))
    )
    (net (code "3") (name "/A02") (class "Default")
      (node (ref "RN7") (pin "1") (pinfunction "1_1") (pintype "passive"))
    )
    (net (code "4") (name "/A03") (class "Default")
      (node (ref "RN7") (pin "4") (pinfunction "4_4") (pintype "passive"))
    )
    (net (code "5") (name "/A04") (class "Default")
      (node (ref "RN5") (pin "1") (pinfunction "1_1") (pintype "passive"))
    )
    (net (code "6") (name "/A05") (class "Default")
      (node (ref "RN7") (pin "2") (pinfunction "2_2") (pintype "passive"))
    )
    (net (code "7") (name "/A06") (class "Default")
      (node (ref "RN2") (pin "4") (pinfunction "4_4") (pintype "passive"))
    )
    (net (code "8") (name "/A07") (class "Default")
      (node (ref "RN7") (pin "3") (pinfunction "3_3") (pintype "passive"))
    )
    (net (code "9") (name "/A08") (class "Default")
      (node (ref "RN5") (pin "4") (pinfunction "4_4") (pintype "passive"))
    )
    (net (code "10") (name "/A09") (class "Default")
      (node (ref "RN6") (pin "1") (pinfunction "1_1") (pintype "passive"))
    )
    (net (code "11") (name "/A10") (class "Default")
      (node (ref "RN3") (pin "1") (pinfunction "1_1") (pintype "passive"))
    )
    (net (code "12") (name "/A11") (class "Default")
      (node (ref "RN6") (pin "4") (pinfunction "4_4") (pintype "passive"))
    )
    (net (code "13") (name "/A12") (class "Default")
      (node (ref "RN4") (pin "3") (pinfunction "3_3") (pintype "passive"))
    )
    (net (code "14") (name "/A13") (class "Default")
      (node (ref "RN6") (pin "3") (pinfunction "3_3") (pintype "passive"))
    )
    (net (code "15") (name "/A14") (class "Default")
      (node (ref "RN2") (pin "3") (pinfunction "3_3") (pintype "passive"))
    )
    (net (code "16") (name "/A15") (class "Default")
      (node (ref "RN3") (pin "4") (pinfunction "4_4") (pintype "passive"))
    )
    (net (code "17") (name "/A16") (class "Default")
      (node (ref "RN4") (pin "2") (pinfunction "2_2") (pintype "passive"))
    )
    (net (code "18") (name "/ACT") (class "Default")
      (node (ref "RN3") (pin "3") (pinfunction "3_3") (pintype "passive"))
    )
    (net (code "19") (name "/BA0") (class "Default")
      (node (ref "RN2") (pin "2") (pinfunction "2_2") (pintype "passive"))
    )
    (net (code "20") (name "/BA1") (class "Default")
      (node (ref "RN4") (pin "1") (pinfunction "1_1") (pintype "passive"))
    )
    (net (code "21") (name "/BG0") (class "Default")
      (node (ref "RN3") (pin "2") (pinfunction "2_2") (pintype "passive"))
    )
    (net (code "22") (name "/BG1") (class "Default")
      (node (ref "RN2") (pin "1") (pinfunction "1_1") (pintype "passive"))
    )
    (net (code "23") (name "/CK0_N") (class "Default")
      (node (ref "R85") (pin "1") (pinfunction "1_1") (pintype "passive"))
    )
    (net (code "24") (name "/CK0_P") (class "Default")
      (node (ref "R80") (pin "1") (pinfunction "1_1") (pintype "passive"))
    )
    (net (code "25") (name "/CKE0") (class "Default")
      (node (ref "RN1") (pin "4") (pinfunction "4_4") (pintype "passive"))
    )
    (net (code "26") (name "/DM0") (class "Default")
      (node (ref "R36") (pin "1") (pinfunction "1_1") (pintype "passive"))
    )
    (net (code "27") (name "/DM0R") (class "Default")
      (node (ref "R36") (pin "2") (pinfunction "2_2") (pintype "passive"))
    )
    (net (code "28") (name "/DM1") (class "Default")
      (node (ref "R56") (pin "1") (pinfunction "1_1") (pintype "passive"))
    )
    (net (code "29") (name "/DM1R") (class "Default")
      (node (ref "R56") (pin "2") (pinfunction "2_2") (pintype "passive"))
    )
    (net (code "30") (name "/DM2") (class "Default")
      (node (ref "R37") (pin "1") (pinfunction "1_1") (pintype "passive"))
    )
    (net (code "31") (name "/DM2R") (class "Default")
      (node (ref "R37") (pin "2") (pinfunction "2_2") (pintype "passive"))
    )
    (net (code "32") (name "/DM3") (class "Default")
      (node (ref "R57") (pin "1") (pinfunction "1_1") (pintype "passive"))
    )
    (net (code "33") (name "/DM3R") (class "Default")
      (node (ref "R57") (pin "2") (pinfunction "2_2") (pintype "passive"))
    )
    (net (code "34") (name "/DM4") (class "Default")
      (node (ref "R38") (pin "1") (pinfunction "1_1") (pintype "passive"))
    )
    (net (code "35") (name "/DM4R") (class "Default")
      (node (ref "R38") (pin "2") (pinfunction "2_2") (pintype "passive"))
    )
    (net (code "36") (name "/DM5") (class "Default")
      (node (ref "R58") (pin "1") (pinfunction "1_1") (pintype "passive"))
    )
    (net (code "37") (name "/DM5R") (class "Default")
      (node (ref "R58") (pin "2") (pinfunction "2_2") (pintype "passive"))
    )
    (net (code "38") (name "/DM6") (class "Default")
      (node (ref "R39") (pin "1") (pinfunction "1_1") (pintype "passive"))
    )
    (net (code "39") (name "/DM6R") (class "Default")
      (node (ref "R39") (pin "2") (pinfunction "2_2") (pintype "passive"))
    )
    (net (code "40") (name "/DM7") (class "Default")
      (node (ref "R59") (pin "1") (pinfunction "1_1") (pintype "passive"))
    )
    (net (code "41") (name "/DM7R") (class "Default")
      (node (ref "R59") (pin "2") (pinfunction "2_2") (pintype "passive"))
    )
    (net (code "42") (name "/DQ00") (class "Default")
      (node (ref "R32") (pin "1") (pinfunction "1_1") (pintype "passive"))
    )
    (net (code "43") (name "/DQ00R") (class "Default")
      (node (ref "R32") (pin "2") (pinfunction "2_2") (pintype "passive"))
    )
    (net (code "44") (name "/DQ01") (class "Default")
      (node (ref "R8") (pin "1") (pinfunction "1_1") (pintype "passive"))
    )
    (net (code "45") (name "/DQ01R") (class "Default")
      (node (ref "R8") (pin "2") (pinfunction "2_2") (pintype "passive"))
    )
    (net (code "46") (name "/DQ02") (class "Default")
      (node (ref "R44") (pin "1") (pinfunction "1_1") (pintype "passive"))
    )
    (net (code "47") (name "/DQ02R") (class "Default")
      (node (ref "R44") (pin "2") (pinfunction "2_2") (pintype "passive"))
    )
    (net (code "48") (name "/DQ03") (class "Default")
      (node (ref "R24") (pin "1") (pinfunction "1_1") (pintype "passive"))
    )
    (net (code "49") (name "/DQ03R") (class "Default")
      (node (ref "R24") (pin "2") (pinfunction "2_2") (pintype "passive"))
    )
    (net (code "50") (name "/DQ04") (class "Default")
      (node (ref "R28") (pin "1") (pinfunction "1_1") (pintype "passive"))
    )
    (net (code "51") (name "/DQ04R") (class "Default")
      (node (ref "R28") (pin "2") (pinfunction "2_2") (pintype "passive"))
    )
    (net (code "52") (name "/DQ05") (class "Default")
      (node (ref "R4") (pin "1") (pinfunction "1_1") (pintype "passive"))
    )
    (net (code "53") (name "/DQ05R") (class "Default")
      (node (ref "R4") (pin "2") (pinfunction "2_2") (pintype "passive"))
    )
    (net (code "54") (name "/DQ06") (class "Default")
      (node (ref "R40") (pin "1") (pinfunction "1_1") (pintype "passive"))
    )
    (net (code "55") (name "/DQ06R") (class "Default")
      (node (ref "R40") (pin "2") (pinfunction "2_2") (pintype "passive"))
    )
    (net (code "56") (name "/DQ07") (class "Default")
      (node (ref "R20") (pin "1") (pinfunction "1_1") (pintype "passive"))
    )
    (net (code "57") (name "/DQ07R") (class "Default")
      (node (ref "R20") (pin "2") (pinfunction "2_2") (pintype "passive"))
    )
    (net (code "58") (name "/DQ08") (class "Default")
      (node (ref "R72") (pin "1") (pinfunction "1_1") (pintype "passive"))
    )
    (net (code "59") (name "/DQ08R") (class "Default")
      (node (ref "R72") (pin "2") (pinfunction "2_2") (pintype "passive"))
    )
    (net (code "60") (name "/DQ09") (class "Default")
      (node (ref "R52") (pin "1") (pinfunction "1_1") (pintype "passive"))
    )
    (net (code "61") (name "/DQ09R") (class "Default")
      (node (ref "R52") (pin "2") (pinfunction "2_2") (pintype "passive"))
    )
    (net (code "62") (name "/DQ10") (class "Default")
      (node (ref "R64") (pin "1") (pinfunction "1_1") (pintype "passive"))
    )
    (net (code "63") (name "/DQ10R") (class "Default")
      (node (ref "R64") (pin "2") (pinfunction "2_2") (pintype "passive"))
    )
    (net (code "64") (name "/DQ11") (class "Default")
      (node (ref "R90") (pin "1") (pinfunction "1_1") (pintype "passive"))
    )
    (net (code "65") (name "/DQ11R") (class "Default")
      (node (ref "R90") (pin "2") (pinfunction "2_2") (pintype "passive"))
    )
    (net (code "66") (name "/DQ12") (class "Default")
      (node (ref "R68") (pin "1") (pinfunction "1_1") (pintype "passive"))
    )
    (net (code "67") (name "/DQ12R") (class "Default")
      (node (ref "R68") (pin "2") (pinfunction "2_2") (pintype "passive"))
    )
    (net (code "68") (name "/DQ13") (class "Default")
      (node (ref "R48") (pin "1") (pinfunction "1_1") (pintype "passive"))
    )
    (net (code "69") (name "/DQ13R") (class "Default")
      (node (ref "R48") (pin "2") (pinfunction "2_2") (pintype "passive"))
    )
    (net (code "70") (name "/DQ14") (class "Default")
      (node (ref "R86") (pin "1") (pinfunction "1_1") (pintype "passive"))
    )
    (net (code "71") (name "/DQ14R") (class "Default")
      (node (ref "R86") (pin "2") (pinfunction "2_2") (pintype "passive"))
    )
    (net (code "72") (name "/DQ15") (class "Default")
      (node (ref "R60") (pin "1") (pinfunction "1_1") (pintype "passive"))
    )
    (net (code "73") (name "/DQ15R") (class "Default")
      (node (ref "R60") (pin "2") (pinfunction "2_2") (pintype "passive"))
    )
    (net (code "74") (name "/DQ16") (class "Default")
      (node (ref "R33") (pin "1") (pinfunction "1_1") (pintype "passive"))
    )
    (net (code "75") (name "/DQ16R") (class "Default")
      (node (ref "R33") (pin "2") (pinfunction "2_2") (pintype "passive"))
    )
    (net (code "76") (name "/DQ17") (class "Default")
      (node (ref "R9") (pin "1") (pinfunction "1_1") (pintype "passive"))
    )
    (net (code "77") (name "/DQ17R") (class "Default")
      (node (ref "R9") (pin "2") (pinfunction "2_2") (pintype "passive"))
    )
    (net (code "78") (name "/DQ18") (class "Default")
      (node (ref "R45") (pin "1") (pinfunction "1_1") (pintype "passive"))
    )
    (net (code "79") (name "/DQ18R") (class "Default")
      (node (ref "R45") (pin "2") (pinfunction "2_2") (pintype "passive"))
    )
    (net (code "80") (name "/DQ19") (class "Default")
      (node (ref "R25") (pin "1") (pinfunction "1_1") (pintype "passive"))
    )
    (net (code "81") (name "/DQ19R") (class "Default")
      (node (ref "R25") (pin "2") (pinfunction "2_2") (pintype "passive"))
    )
    (net (code "82") (name "/DQ20") (class "Default")
      (node (ref "R29") (pin "1") (pinfunction "1_1") (pintype "passive"))
    )
    (net (code "83") (name "/DQ20R") (class "Default")
      (node (ref "R29") (pin "2") (pinfunction "2_2") (pintype "passive"))
    )
    (net (code "84") (name "/DQ21") (class "Default")
      (node (ref "R5") (pin "1") (pinfunction "1_1") (pintype "passive"))
    )
    (net (code "85") (name "/DQ21R") (class "Default")
      (node (ref "R5") (pin "2") (pinfunction "2_2") (pintype "passive"))
    )
    (net (code "86") (name "/DQ22") (class "Default")
      (node (ref "R41") (pin "1") (pinfunction "1_1") (pintype "passive"))
    )
    (net (code "87") (name "/DQ22R") (class "Default")
      (node (ref "R41") (pin "2") (pinfunction "2_2") (pintype "passive"))
    )
    (net (code "88") (name "/DQ23") (class "Default")
      (node (ref "R21") (pin "1") (pinfunction "1_1") (pintype "passive"))
    )
    (net (code "89") (name "/DQ23R") (class "Default")
      (node (ref "R21") (pin "2") (pinfunction "2_2") (pintype "passive"))
    )
    (net (code "90") (name "/DQ24") (class "Default")
      (node (ref "R73") (pin "1") (pinfunction "1_1") (pintype "passive"))
    )
    (net (code "91") (name "/DQ24R") (class "Default")
      (node (ref "R73") (pin "2") (pinfunction "2_2") (pintype "passive"))
    )
    (net (code "92") (name "/DQ25") (class "Default")
      (node (ref "R53") (pin "1") (pinfunction "1_1") (pintype "passive"))
    )
    (net (code "93") (name "/DQ25R") (class "Default")
      (node (ref "R53") (pin "2") (pinfunction "2_2") (pintype "passive"))
    )
    (net (code "94") (name "/DQ26") (class "Default")
      (node (ref "R65") (pin "1") (pinfunction "1_1") (pintype "passive"))
    )
    (net (code "95") (name "/DQ26R") (class "Default")
      (node (ref "R65") (pin "2") (pinfunction "2_2") (pintype "passive"))
    )
    (net (code "96") (name "/DQ27") (class "Default")
      (node (ref "R91") (pin "1") (pinfunction "1_1") (pintype "passive"))
    )
    (net (code "97") (name "/DQ27R") (class "Default")
      (node (ref "R91") (pin "2") (pinfunction "2_2") (pintype "passive"))
    )
    (net (code "98") (name "/DQ28") (class "Default")
      (node (ref "R69") (pin "1") (pinfunction "1_1") (pintype "passive"))
    )
    (net (code "99") (name "/DQ28R") (class "Default")
      (node (ref "R69") (pin "2") (pinfunction "2_2") (pintype "passive"))
    )
    (net (code "100") (name "/DQ29") (class "Default")
      (node (ref "R49") (pin "1") (pinfunction "1_1") (pintype "passive"))
    )
    (net (code "101") (name "/DQ29R") (class "Default")
      (node (ref "R49") (pin "2") (pinfunction "2_2") (pintype "passive"))
    )
    (net (code "102") (name "/DQ30") (class "Default")
      (node (ref "R61") (pin "1") (pinfunction "1_1") (pintype "passive"))
    )
    (net (code "103") (name "/DQ30R") (class "Default")
      (node (ref "R61") (pin "2") (pinfunction "2_2") (pintype "passive"))
    )
    (net (code "104") (name "/DQ31") (class "Default")
      (node (ref "R87") (pin "1") (pinfunction "1_1") (pintype "passive"))
    )
    (net (code "105") (name "/DQ31R") (class "Default")
      (node (ref "R87") (pin "2") (pinfunction "2_2") (pintype "passive"))
    )
    (net (code "106") (name "/DQ32") (class "Default")
      (node (ref "R34") (pin "1") (pinfunction "1_1") (pintype "passive"))
    )
    (net (code "107") (name "/DQ32R") (class "Default")
      (node (ref "R34") (pin "2") (pinfunction "2_2") (pintype "passive"))
    )
    (net (code "108") (name "/DQ33") (class "Default")
      (node (ref "R10") (pin "1") (pinfunction "1_1") (pintype "passive"))
    )
    (net (code "109") (name "/DQ33R") (class "Default")
      (node (ref "R10") (pin "2") (pinfunction "2_2") (pintype "passive"))
    )
    (net (code "110") (name "/DQ34") (class "Default")
      (node (ref "R26") (pin "1") (pinfunction "1_1") (pintype "passive"))
    )
    (net (code "111") (name "/DQ34R") (class "Default")
      (node (ref "R26") (pin "2") (pinfunction "2_2") (pintype "passive"))
    )
    (net (code "112") (name "/DQ35") (class "Default")
      (node (ref "R46") (pin "1") (pinfunction "1_1") (pintype "passive"))
    )
    (net (code "113") (name "/DQ35R") (class "Default")
      (node (ref "R46") (pin "2") (pinfunction "2_2") (pintype "passive"))
    )
    (net (code "114") (name "/DQ36") (class "Default")
      (node (ref "R30") (pin "1") (pinfunction "1_1") (pintype "passive"))
    )
    (net (code "115") (name "/DQ36R") (class "Default")
      (node (ref "R30") (pin "2") (pinfunction "2_2") (pintype "passive"))
    )
    (net (code "116") (name "/DQ37") (class "Default")
      (node (ref "R6") (pin "1") (pinfunction "1_1") (pintype "passive"))
    )
    (net (code "117") (name "/DQ37R") (class "Default")
      (node (ref "R6") (pin "2") (pinfunction "2_2") (pintype "passive"))
    )
    (net (code "118") (name "/DQ38") (class "Default")
      (node (ref "R22") (pin "1") (pinfunction "1_1") (pintype "passive"))
    )
    (net (code "119") (name "/DQ38R") (class "Default")
      (node (ref "R22") (pin "2") (pinfunction "2_2") (pintype "passive"))
    )
    (net (code "120") (name "/DQ39") (class "Default")
      (node (ref "R42") (pin "1") (pinfunction "1_1") (pintype "passive"))
    )
    (net (code "121") (name "/DQ39R") (class "Default")
      (node (ref "R42") (pin "2") (pinfunction "2_2") (pintype "passive"))
    )
    (net (code "122") (name "/DQ40") (class "Default")
      (node (ref "R54") (pin "1") (pinfunction "1_1") (pintype "passive"))
    )
    (net (code "123") (name "/DQ40R") (class "Default")
      (node (ref "R54") (pin "2") (pinfunction "2_2") (pintype "passive"))
    )
    (net (code "124") (name "/DQ41") (class "Default")
      (node (ref "R74") (pin "1") (pinfunction "1_1") (pintype "passive"))
    )
    (net (code "125") (name "/DQ41R") (class "Default")
      (node (ref "R74") (pin "2") (pinfunction "2_2") (pintype "passive"))
    )
    (net (code "126") (name "/DQ42") (class "Default")
      (node (ref "R66") (pin "1") (pinfunction "1_1") (pintype "passive"))
    )
    (net (code "127") (name "/DQ42R") (class "Default")
      (node (ref "R66") (pin "2") (pinfunction "2_2") (pintype "passive"))
    )
    (net (code "128") (name "/DQ43") (class "Default")
      (node (ref "R92") (pin "1") (pinfunction "1_1") (pintype "passive"))
    )
    (net (code "129") (name "/DQ43R") (class "Default")
      (node (ref "R92") (pin "2") (pinfunction "2_2") (pintype "passive"))
    )
    (net (code "130") (name "/DQ44") (class "Default")
      (node (ref "R50") (pin "1") (pinfunction "1_1") (pintype "passive"))
    )
    (net (code "131") (name "/DQ44R") (class "Default")
      (node (ref "R50") (pin "2") (pinfunction "2_2") (pintype "passive"))
    )
    (net (code "132") (name "/DQ45") (class "Default")
      (node (ref "R70") (pin "1") (pinfunction "1_1") (pintype "passive"))
    )
    (net (code "133") (name "/DQ45R") (class "Default")
      (node (ref "R70") (pin "2") (pinfunction "2_2") (pintype "passive"))
    )
    (net (code "134") (name "/DQ46") (class "Default")
      (node (ref "R62") (pin "1") (pinfunction "1_1") (pintype "passive"))
    )
    (net (code "135") (name "/DQ46R") (class "Default")
      (node (ref "R62") (pin "2") (pinfunction "2_2") (pintype "passive"))
    )
    (net (code "136") (name "/DQ47") (class "Default")
      (node (ref "R88") (pin "1") (pinfunction "1_1") (pintype "passive"))
    )
    (net (code "137") (name "/DQ47R") (class "Default")
      (node (ref "R88") (pin "2") (pinfunction "2_2") (pintype "passive"))
    )
    (net (code "138") (name "/DQ48") (class "Default")
      (node (ref "R35") (pin "1") (pinfunction "1_1") (pintype "passive"))
    )
    (net (code "139") (name "/DQ48R") (class "Default")
      (node (ref "R35") (pin "2") (pinfunction "2_2") (pintype "passive"))
    )
    (net (code "140") (name "/DQ49") (class "Default")
      (node (ref "R11") (pin "1") (pinfunction "1_1") (pintype "passive"))
    )
    (net (code "141") (name "/DQ49R") (class "Default")
      (node (ref "R11") (pin "2") (pinfunction "2_2") (pintype "passive"))
    )
    (net (code "142") (name "/DQ50") (class "Default")
      (node (ref "R47") (pin "1") (pinfunction "1_1") (pintype "passive"))
    )
    (net (code "143") (name "/DQ50R") (class "Default")
      (node (ref "R47") (pin "2") (pinfunction "2_2") (pintype "passive"))
    )
    (net (code "144") (name "/DQ51") (class "Default")
      (node (ref "R27") (pin "1") (pinfunction "1_1") (pintype "passive"))
    )
    (net (code "145") (name "/DQ51R") (class "Default")
      (node (ref "R27") (pin "2") (pinfunction "2_2") (pintype "passive"))
    )
    (net (code "146") (name "/DQ52") (class "Default")
      (node (ref "R7") (pin "1") (pinfunction "1_1") (pintype "passive"))
    )
    (net (code "147") (name "/DQ52R") (class "Default")
      (node (ref "R7") (pin "2") (pinfunction "2_2") (pintype "passive"))
    )
    (net (code "148") (name "/DQ53") (class "Default")
      (node (ref "R31") (pin "1") (pinfunction "1_1") (pintype "passive"))
    )
    (net (code "149") (name "/DQ53R") (class "Default")
      (node (ref "R31") (pin "2") (pinfunction "2_2") (pintype "passive"))
    )
    (net (code "150") (name "/DQ54") (class "Default")
      (node (ref "R43") (pin "1") (pinfunction "1_1") (pintype "passive"))
    )
    (net (code "151") (name "/DQ54R") (class "Default")
      (node (ref "R43") (pin "2") (pinfunction "2_2") (pintype "passive"))
    )
    (net (code "152") (name "/DQ55") (class "Default")
      (node (ref "R23") (pin "1") (pinfunction "1_1") (pintype "passive"))
    )
    (net (code "153") (name "/DQ55R") (class "Default")
      (node (ref "R23") (pin "2") (pinfunction "2_2") (pintype "passive"))
    )
    (net (code "154") (name "/DQ56") (class "Default")
      (node (ref "R55") (pin "1") (pinfunction "1_1") (pintype "passive"))
    )
    (net (code "155") (name "/DQ56R") (class "Default")
      (node (ref "R55") (pin "2") (pinfunction "2_2") (pintype "passive"))
    )
    (net (code "156") (name "/DQ57") (class "Default")
      (node (ref "R75") (pin "1") (pinfunction "1_1") (pintype "passive"))
    )
    (net (code "157") (name "/DQ57R") (class "Default")
      (node (ref "R75") (pin "2") (pinfunction "2_2") (pintype "passive"))
    )
    (net (code "158") (name "/DQ58") (class "Default")
      (node (ref "R67") (pin "1") (pinfunction "1_1") (pintype "passive"))
    )
    (net (code "159") (name "/DQ58R") (class "Default")
      (node (ref "R67") (pin "2") (pinfunction "2_2") (pintype "passive"))
    )
    (net (code "160") (name "/DQ59") (class "Default")
      (node (ref "R93") (pin "1") (pinfunction "1_1") (pintype "passive"))
    )
    (net (code "161") (name "/DQ59R") (class "Default")
      (node (ref "R93") (pin "2") (pinfunction "2_2") (pintype "passive"))
    )
    (net (code "162") (name "/DQ60") (class "Default")
      (node (ref "R71") (pin "1") (pinfunction "1_1") (pintype "passive"))
    )
    (net (code "163") (name "/DQ60R") (class "Default")
      (node (ref "R71") (pin "2") (pinfunction "2_2") (pintype "passive"))
    )
    (net (code "164") (name "/DQ61") (class "Default")
      (node (ref "R51") (pin "1") (pinfunction "1_1") (pintype "passive"))
    )
    (net (code "165") (name "/DQ61R") (class "Default")
      (node (ref "R51") (pin "2") (pinfunction "2_2") (pintype "passive"))
    )
    (net (code "166") (name "/DQ62") (class "Default")
      (node (ref "R63") (pin "1") (pinfunction "1_1") (pintype "passive"))
    )
    (net (code "167") (name "/DQ62R") (class "Default")
      (node (ref "R63") (pin "2") (pinfunction "2_2") (pintype "passive"))
    )
    (net (code "168") (name "/DQ63") (class "Default")
      (node (ref "R89") (pin "1") (pinfunction "1_1") (pintype "passive"))
    )
    (net (code "169") (name "/DQ63R") (class "Default")
      (node (ref "R89") (pin "2") (pinfunction "2_2") (pintype "passive"))
    )
    (net (code "170") (name "/DQS0R_N") (class "Default")
      (node (ref "R12") (pin "2") (pinfunction "2_2") (pintype "passive"))
    )
    (net (code "171") (name "/DQS0R_P") (class "Default")
      (node (ref "R16") (pin "2") (pinfunction "2_2") (pintype "passive"))
    )
    (net (code "172") (name "/DQS0_N") (class "Default")
      (node (ref "R12") (pin "1") (pinfunction "1_1") (pintype "passive"))
    )
    (net (code "173") (name "/DQS0_P") (class "Default")
      (node (ref "R16") (pin "1") (pinfunction "1_1") (pintype "passive"))
    )
    (net (code "174") (name "/DQS1R_N") (class "Default")
      (node (ref "R76") (pin "2") (pinfunction "2_2") (pintype "passive"))
    )
    (net (code "175") (name "/DQS1R_P") (class "Default")
      (node (ref "R81") (pin "2") (pinfunction "2_2") (pintype "passive"))
    )
    (net (code "176") (name "/DQS1_N") (class "Default")
      (node (ref "R76") (pin "1") (pinfunction "1_1") (pintype "passive"))
    )
    (net (code "177") (name "/DQS1_P") (class "Default")
      (node (ref "R81") (pin "1") (pinfunction "1_1") (pintype "passive"))
    )
    (net (code "178") (name "/DQS2R_N") (class "Default")
      (node (ref "R13") (pin "2") (pinfunction "2_2") (pintype "passive"))
    )
    (net (code "179") (name "/DQS2R_P") (class "Default")
      (node (ref "R17") (pin "2") (pinfunction "2_2") (pintype "passive"))
    )
    (net (code "180") (name "/DQS2_N") (class "Default")
      (node (ref "R13") (pin "1") (pinfunction "1_1") (pintype "passive"))
    )
    (net (code "181") (name "/DQS2_P") (class "Default")
      (node (ref "R17") (pin "1") (pinfunction "1_1") (pintype "passive"))
    )
    (net (code "182") (name "/DQS3R_N") (class "Default")
      (node (ref "R77") (pin "2") (pinfunction "2_2") (pintype "passive"))
    )
    (net (code "183") (name "/DQS3R_P") (class "Default")
      (node (ref "R82") (pin "2") (pinfunction "2_2") (pintype "passive"))
    )
    (net (code "184") (name "/DQS3_N") (class "Default")
      (node (ref "R77") (pin "1") (pinfunction "1_1") (pintype "passive"))
    )
    (net (code "185") (name "/DQS3_P") (class "Default")
      (node (ref "R82") (pin "1") (pinfunction "1_1") (pintype "passive"))
    )
    (net (code "186") (name "/DQS4R_N") (class "Default")
      (node (ref "R14") (pin "2") (pinfunction "2_2") (pintype "passive"))
    )
    (net (code "187") (name "/DQS4R_P") (class "Default")
      (node (ref "R18") (pin "2") (pinfunction "2_2") (pintype "passive"))
    )
    (net (code "188") (name "/DQS4_N") (class "Default")
      (node (ref "R14") (pin "1") (pinfunction "1_1") (pintype "passive"))
    )
    (net (code "189") (name "/DQS4_P") (class "Default")
      (node (ref "R18") (pin "1") (pinfunction "1_1") (pintype "passive"))
    )
    (net (code "190") (name "/DQS5R_N") (class "Default")
      (node (ref "R78") (pin "2") (pinfunction "2_2") (pintype "passive"))
    )
    (net (code "191") (name "/DQS5R_P") (class "Default")
      (node (ref "R83") (pin "2") (pinfunction "2_2") (pintype "passive"))
    )
    (net (code "192") (name "/DQS5_N") (class "Default")
      (node (ref "R78") (pin "1") (pinfunction "1_1") (pintype "passive"))
    )
    (net (code "193") (name "/DQS5_P") (class "Default")
      (node (ref "R83") (pin "1") (pinfunction "1_1") (pintype "passive"))
    )
    (net (code "194") (name "/DQS6R_N") (class "Default")
      (node (ref "R15") (pin "2") (pinfunction "2_2") (pintype "passive"))
    )
    (net (code "195") (name "/DQS6R_P") (class "Default")
      (node (ref "R19") (pin "2") (pinfunction "2_2") (pintype "passive"))
    )
    (net (code "196") (name "/DQS6_N") (class "Default")
      (node (ref "R15") (pin "1") (pinfunction "1_1") (pintype "passive"))
    )
    (net (code "197") (name "/DQS6_P") (class "Default")
      (node (ref "R19") (pin "1") (pinfunction "1_1") (pintype "passive"))
    )
    (net (code "198") (name "/DQS7R_N") (class "Default")
      (node (ref "R79") (pin "2") (pinfunction "2_2") (pintype "passive"))
    )
    (net (code "199") (name "/DQS7R_P") (class "Default")
      (node (ref "R84") (pin "2") (pinfunction "2_2") (pintype "passive"))
    )
    (net (code "200") (name "/DQS7_N") (class "Default")
      (node (ref "R79") (pin "1") (pinfunction "1_1") (pintype "passive"))
    )
    (net (code "201") (name "/DQS7_P") (class "Default")
      (node (ref "R84") (pin "1") (pinfunction "1_1") (pintype "passive"))
    )
    (net (code "202") (name "/ODT0") (class "Default")
      (node (ref "RN1") (pin "2") (pinfunction "2_2") (pintype "passive"))
    )
    (net (code "203") (name "/PARITY") (class "Default")
      (node (ref "RN6") (pin "2") (pinfunction "2_2") (pintype "passive"))
    )
    (net (code "204") (name "/S0") (class "Default")
      (node (ref "RN1") (pin "1") (pinfunction "1_1") (pintype "passive"))
    )
    (net (code "205") (name "/VDD") (class "Default")
      (node (ref "C4") (pin "2") (pinfunction "2_2") (pintype "passive"))
    )
    (net (code "206") (name "/VTT") (class "Default")
      (node (ref "RN1") (pin "5") (pinfunction "5_5") (pintype "passive"))
      (node (ref "RN1") (pin "6") (pinfunction "6_6") (pintype "passive"))
      (node (ref "RN1") (pin "7") (pinfunction "7_7") (pintype "passive"))
      (node (ref "RN1") (pin "8") (pinfunction "8_8") (pintype "passive"))
      (node (ref "RN2") (pin "5") (pinfunction "5_5") (pintype "passive"))
      (node (ref "RN2") (pin "6") (pinfunction "6_6") (pintype "passive"))
      (node (ref "RN2") (pin "7") (pinfunction "7_7") (pintype "passive"))
      (node (ref "RN2") (pin "8") (pinfunction "8_8") (pintype "passive"))
      (node (ref "RN3") (pin "5") (pinfunction "5_5") (pintype "passive"))
      (node (ref "RN3") (pin "6") (pinfunction "6_6") (pintype "passive"))
      (node (ref "RN3") (pin "7") (pinfunction "7_7") (pintype "passive"))
      (node (ref "RN3") (pin "8") (pinfunction "8_8") (pintype "passive"))
      (node (ref "RN4") (pin "5") (pinfunction "5_5") (pintype "passive"))
      (node (ref "RN4") (pin "6") (pinfunction "6_6") (pintype "passive"))
      (node (ref "RN4") (pin "7") (pinfunction "7_7") (pintype "passive"))
      (node (ref "RN4") (pin "8") (pinfunction "8_8") (pintype "passive"))
      (node (ref "RN5") (pin "5") (pinfunction "5_5") (pintype "passive"))
      (node (ref "RN5") (pin "6") (pinfunction "6_6") (pintype "passive"))
      (node (ref "RN5") (pin "7") (pinfunction "7_7") (pintype "passive"))
      (node (ref "RN5") (pin "8") (pinfunction "8_8") (pintype "passive"))
      (node (ref "RN6") (pin "5") (pinfunction "5_5") (pintype "passive"))
      (node (ref "RN6") (pin "6") (pinfunction "6_6") (pintype "passive"))
      (node (ref "RN6") (pin "7") (pinfunction "7_7") (pintype "passive"))
      (node (ref "RN6") (pin "8") (pinfunction "8_8") (pintype "passive"))
      (node (ref "RN7") (pin "5") (pinfunction "5_5") (pintype "passive"))
      (node (ref "RN7") (pin "6") (pinfunction "6_6") (pintype "passive"))
      (node (ref "RN7") (pin "7") (pinfunction "7_7") (pintype "passive"))
      (node (ref "RN7") (pin "8") (pinfunction "8_8") (pintype "passive"))
    )
    (net (code "207") (name "Net-(C4-Pad1)") (class "Default")
      (node (ref "C4") (pin "1") (pinfunction "1_1") (pintype "passive"))
      (node (ref "R80") (pin "2") (pinfunction "2_2") (pintype "passive"))
      (node (ref "R85") (pin "2") (pinfunction "2_2") (pintype "passive"))
    )
    (net (code "208") (name "unconnected-(RN1-Pad3)") (class "Default")
      (node (ref "RN1") (pin "3") (pinfunction "3_3") (pintype "passive"))
    )
    (net (code "209") (name "unconnected-(RN4-Pad4)") (class "Default")
      (node (ref "RN4") (pin "4") (pinfunction "4_4") (pintype "passive"))
    )
  )
)
